# Sheet1.net
KiCad netlist of a schematic drawn in Altium Designer
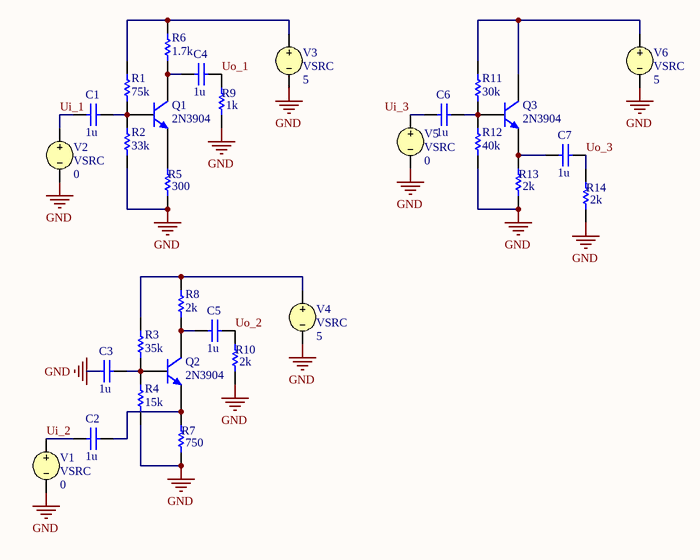
[diagram p0: Sheet1.SchDoc]

(export (version "E")
  (design (tool "Eeschema 10.0.6"))
  (components
    (comp (ref "C1")
      (value "1u")
      (description "Capacitor")
      (libsource (lib "Simulation Generic Components") (part "Capacitor"))
    )
    (comp (ref "C2")
      (value "1u")
      (description "Capacitor")
      (libsource (lib "Simulation Generic Components") (part "Capacitor"))
    )
    (comp (ref "C3")
      (value "1u")
      (description "Capacitor")
      (libsource (lib "Simulation Generic Components") (part "Capacitor"))
    )
    (comp (ref "C4")
      (value "1u")
      (description "Capacitor")
      (libsource (lib "Simulation Generic Components") (part "Capacitor"))
    )
    (comp (ref "C5")
      (value "1u")
      (description "Capacitor")
      (libsource (lib "Simulation Generic Components") (part "Capacitor"))
    )
    (comp (ref "C6")
      (value "1u")
      (description "Capacitor")
      (libsource (lib "Simulation Generic Components") (part "Capacitor"))
    )
    (comp (ref "C7")
      (value "1u")
      (description "Capacitor")
      (libsource (lib "Simulation Generic Components") (part "Capacitor"))
    )
    (comp (ref "Q1")
      (value "2N3904")
      (footprint "TO-92A")
      (description "NPN General Purpose Amplifier")
      (fields (field (name "PUBLISHER") "Altium Limited"))
      (libsource (lib "Miscellaneous Devices") (part "2N3904"))
    )
    (comp (ref "Q2")
      (value "2N3904")
      (footprint "TO-92A")
      (description "NPN General Purpose Amplifier")
      (fields (field (name "PUBLISHER") "Altium Limited"))
      (libsource (lib "Miscellaneous Devices") (part "2N3904"))
    )
    (comp (ref "Q3")
      (value "2N3904")
      (footprint "TO-92A")
      (description "NPN General Purpose Amplifier")
      (fields (field (name "PUBLISHER") "Altium Limited"))
      (libsource (lib "Miscellaneous Devices") (part "2N3904"))
    )
    (comp (ref "R1")
      (value "75k")
      (description "Resistor")
      (libsource (lib "Simulation Generic Components") (part "Resistor"))
    )
    (comp (ref "R2")
      (value "33k")
      (description "Resistor")
      (libsource (lib "Simulation Generic Components") (part "Resistor"))
    )
    (comp (ref "R3")
      (value "35k")
      (description "Resistor")
      (libsource (lib "Simulation Generic Components") (part "Resistor"))
    )
    (comp (ref "R4")
      (value "15k")
      (description "Resistor")
      (libsource (lib "Simulation Generic Components") (part "Resistor"))
    )
    (comp (ref "R5")
      (value "300")
      (description "Resistor")
      (libsource (lib "Simulation Generic Components") (part "Resistor"))
    )
    (comp (ref "R6")
      (value "1.7k")
      (description "Resistor")
      (libsource (lib "Simulation Generic Components") (part "Resistor"))
    )
    (comp (ref "R7")
      (value "750")
      (description "Resistor")
      (libsource (lib "Simulation Generic Components") (part "Resistor"))
    )
    (comp (ref "R8")
      (value "2k")
      (description "Resistor")
      (libsource (lib "Simulation Generic Components") (part "Resistor"))
    )
    (comp (ref "R9")
      (value "1k")
      (description "Resistor")
      (libsource (lib "Simulation Generic Components") (part "Resistor"))
    )
    (comp (ref "R10")
      (value "2k")
      (description "Resistor")
      (libsource (lib "Simulation Generic Components") (part "Resistor"))
    )
    (comp (ref "R11")
      (value "30k")
      (description "Resistor")
      (libsource (lib "Simulation Generic Components") (part "Resistor"))
    )
    (comp (ref "R12")
      (value "40k")
      (description "Resistor")
      (libsource (lib "Simulation Generic Components") (part "Resistor"))
    )
    (comp (ref "R13")
      (value "2k")
      (description "Resistor")
      (libsource (lib "Simulation Generic Components") (part "Resistor"))
    )
    (comp (ref "R14")
      (value "2k")
      (description "Resistor")
      (libsource (lib "Simulation Generic Components") (part "Resistor"))
    )
    (comp (ref "V1")
      (value "VSRC")
      (description "Voltage Source")
      (fields (field (name "DC MAGNITUDE") "0") (field (name "PUBLISHER") "Altium Limited"))
      (libsource (lib "Simulation Generic Components") (part "VSRC"))
    )
    (comp (ref "V2")
      (value "VSRC")
      (description "Voltage Source")
      (fields (field (name "DC MAGNITUDE") "0") (field (name "PUBLISHER") "Altium Limited"))
      (libsource (lib "Simulation Generic Components") (part "VSRC"))
    )
    (comp (ref "V3")
      (value "VSRC")
      (description "Voltage Source")
      (fields (field (name "ALTIUM_VALUE") "5") (field (name "PUBLISHER") "Altium Limited"))
      (libsource (lib "Simulation Generic Components") (part "VSRC"))
    )
    (comp (ref "V4")
      (value "VSRC")
      (description "Voltage Source")
      (fields (field (name "ALTIUM_VALUE") "5") (field (name "PUBLISHER") "Altium Limited"))
      (libsource (lib "Simulation Generic Components") (part "VSRC"))
    )
    (comp (ref "V5")
      (value "VSRC")
      (description "Voltage Source")
      (fields (field (name "DC MAGNITUDE") "0") (field (name "PUBLISHER") "Altium Limited"))
      (libsource (lib "Simulation Generic Components") (part "VSRC"))
    )
    (comp (ref "V6")
      (value "VSRC")
      (description "Voltage Source")
      (fields (field (name "ALTIUM_VALUE") "5") (field (name "PUBLISHER") "Altium Limited"))
      (libsource (lib "Simulation Generic Components") (part "VSRC"))
    )
  )
  (nets
    (net (code "1") (name "/Ui_1") (class "Default")
      (node (ref "C1") (pin "1") (pinfunction "1_1") (pintype "passive"))
      (node (ref "V2") (pin "1") (pinfunction "1_1") (pintype "passive"))
    )
    (net (code "2") (name "/Ui_2") (class "Default")
      (node (ref "C2") (pin "1") (pinfunction "1_1") (pintype "passive"))
      (node (ref "V1") (pin "1") (pinfunction "1_1") (pintype "passive"))
    )
    (net (code "3") (name "/Ui_3") (class "Default")
      (node (ref "C6") (pin "1") (pinfunction "1_1") (pintype "passive"))
      (node (ref "V5") (pin "1") (pinfunction "1_1") (pintype "passive"))
    )
    (net (code "4") (name "/Uo_1") (class "Default")
      (node (ref "C4") (pin "2") (pinfunction "2_2") (pintype "passive"))
      (node (ref "R9") (pin "2") (pinfunction "2_2") (pintype "passive"))
    )
    (net (code "5") (name "/Uo_2") (class "Default")
      (node (ref "C5") (pin "2") (pinfunction "2_2") (pintype "passive"))
      (node (ref "R10") (pin "2") (pinfunction "2_2") (pintype "passive"))
    )
    (net (code "6") (name "/Uo_3") (class "Default")
      (node (ref "C7") (pin "2") (pinfunction "2_2") (pintype "passive"))
      (node (ref "R14") (pin "2") (pinfunction "2_2") (pintype "passive"))
    )
    (net (code "7") (name "GND") (class "Default")
      (node (ref "C3") (pin "1") (pinfunction "1_1") (pintype "passive"))
      (node (ref "R10") (pin "1") (pinfunction "1_1") (pintype "passive"))
      (node (ref "R12") (pin "1") (pinfunction "1_1") (pintype "passive"))
      (node (ref "R13") (pin "1") (pinfunction "1_1") (pintype "passive"))
      (node (ref "R14") (pin "1") (pinfunction "1_1") (pintype "passive"))
      (node (ref "R2") (pin "1") (pinfunction "1_1") (pintype "passive"))
      (node (ref "R4") (pin "1") (pinfunction "1_1") (pintype "passive"))
      (node (ref "R5") (pin "1") (pinfunction "1_1") (pintype "passive"))
      (node (ref "R7") (pin "1") (pinfunction "1_1") (pintype "passive"))
      (node (ref "R9") (pin "1") (pinfunction "1_1") (pintype "passive"))
      (node (ref "V1") (pin "2") (pinfunction "2_2") (pintype "passive"))
      (node (ref "V2") (pin "2") (pinfunction "2_2") (pintype "passive"))
      (node (ref "V3") (pin "2") (pinfunction "2_2") (pintype "passive"))
      (node (ref "V4") (pin "2") (pinfunction "2_2") (pintype "passive"))
      (node (ref "V5") (pin "2") (pinfunction "2_2") (pintype "passive"))
      (node (ref "V6") (pin "2") (pinfunction "2_2") (pintype "passive"))
    )
    (net (code "8") (name "Net-(Q1-B)") (class "Default")
      (node (ref "C1") (pin "2") (pinfunction "2_2") (pintype "passive"))
      (node (ref "Q1") (pin "2") (pinfunction "B_2") (pintype "passive"))
      (node (ref "R1") (pin "1") (pinfunction "1_1") (pintype "passive"))
      (node (ref "R2") (pin "2") (pinfunction "2_2") (pintype "passive"))
    )
    (net (code "9") (name "Net-(Q1-C)") (class "Default")
      (node (ref "C4") (pin "1") (pinfunction "1_1") (pintype "passive"))
      (node (ref "Q1") (pin "3") (pinfunction "C_3") (pintype "passive"))
      (node (ref "R6") (pin "1") (pinfunction "1_1") (pintype "passive"))
    )
    (net (code "10") (name "Net-(Q1-E)") (class "Default")
      (node (ref "Q1") (pin "1") (pinfunction "E_1") (pintype "passive"))
      (node (ref "R5") (pin "2") (pinfunction "2_2") (pintype "passive"))
    )
    (net (code "11") (name "Net-(Q2-B)") (class "Default")
      (node (ref "C3") (pin "2") (pinfunction "2_2") (pintype "passive"))
      (node (ref "Q2") (pin "2") (pinfunction "B_2") (pintype "passive"))
      (node (ref "R3") (pin "1") (pinfunction "1_1") (pintype "passive"))
      (node (ref "R4") (pin "2") (pinfunction "2_2") (pintype "passive"))
    )
    (net (code "12") (name "Net-(Q2-C)") (class "Default")
      (node (ref "C5") (pin "1") (pinfunction "1_1") (pintype "passive"))
      (node (ref "Q2") (pin "3") (pinfunction "C_3") (pintype "passive"))
      (node (ref "R8") (pin "1") (pinfunction "1_1") (pintype "passive"))
    )
    (net (code "13") (name "Net-(Q2-E)") (class "Default")
      (node (ref "C2") (pin "2") (pinfunction "2_2") (pintype "passive"))
      (node (ref "Q2") (pin "1") (pinfunction "E_1") (pintype "passive"))
      (node (ref "R7") (pin "2") (pinfunction "2_2") (pintype "passive"))
    )
    (net (code "14") (name "Net-(Q3-B)") (class "Default")
      (node (ref "C6") (pin "2") (pinfunction "2_2") (pintype "passive"))
      (node (ref "Q3") (pin "2") (pinfunction "B_2") (pintype "passive"))
      (node (ref "R11") (pin "1") (pinfunction "1_1") (pintype "passive"))
      (node (ref "R12") (pin "2") (pinfunction "2_2") (pintype "passive"))
    )
    (net (code "15") (name "Net-(Q3-C)") (class "Default")
      (node (ref "Q3") (pin "3") (pinfunction "C_3") (pintype "passive"))
      (node (ref "R11") (pin "2") (pinfunction "2_2") (pintype "passive"))
      (node (ref "V6") (pin "1") (pinfunction "1_1") (pintype "passive"))
    )
    (net (code "16") (name "Net-(Q3-E)") (class "Default")
      (node (ref "C7") (pin "1") (pinfunction "1_1") (pintype "passive"))
      (node (ref "Q3") (pin "1") (pinfunction "E_1") (pintype "passive"))
      (node (ref "R13") (pin "2") (pinfunction "2_2") (pintype "passive"))
    )
    (net (code "17") (name "Net-(R1-Pad2)") (class "Default")
      (node (ref "R1") (pin "2") (pinfunction "2_2") (pintype "passive"))
      (node (ref "R6") (pin "2") (pinfunction "2_2") (pintype "passive"))
      (node (ref "V3") (pin "1") (pinfunction "1_1") (pintype "passive"))
    )
    (net (code "18") (name "Net-(R3-Pad2)") (class "Default")
      (node (ref "R3") (pin "2") (pinfunction "2_2") (pintype "passive"))
      (node (ref "R8") (pin "2") (pinfunction "2_2") (pintype "passive"))
      (node (ref "V4") (pin "1") (pinfunction "1_1") (pintype "passive"))
    )
  )
)
